# MCU.net
KiCad netlist of a schematic drawn in Altium Designer
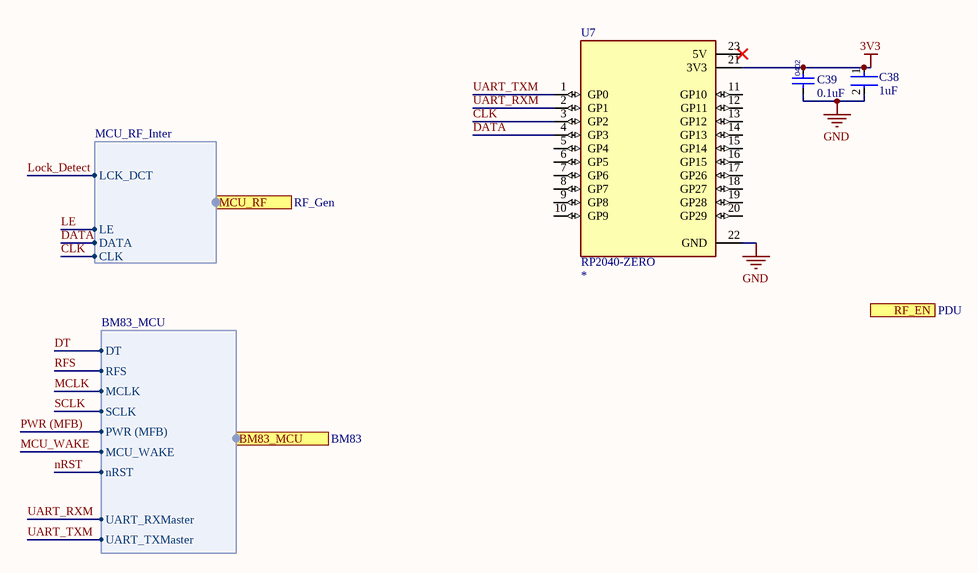
[diagram p0: MCU.SchDoc]

(export (version "E")
  (design (tool "Eeschema 10.0.6"))
  (components
    (comp (ref "C38")
      (value "1uF")
      (footprint "FP-GRM155-0_1-IPC_C")
      (libsource (lib "Altium Content Vault") (part "11868f565c42a9108669ba33697ecf6"))
    )
    (comp (ref "C39")
      (value "0.1uF")
      (footprint "FP-CC0402-IPC_B")
      (fields (field (name "TOLERANCE") "10%"))
      (libsource (lib "University of Wisconsin Formula FSAE") (part "0402 ceramic cap"))
    )
    (comp (ref "U7")
      (value "RP2040-ZERO")
      (footprint "MODULE_RP2040-ZERO")
      (description "Low-Cost, High-Performance Pico-Like MCU Board Based On Raspberry Pi Microcontroller RP2040")
      (fields (field (name "ALTIUM_VALUE") "*") (field (name "MF") "Waveshare Electronics"))
      (libsource (lib "University of Wisconsin Formula FSAE") (part "RP2040-ZERO"))
    )
  )
  (nets
    (net (code "3") (name "/CLK") (class "Default")
      (node (ref "U7") (pin "3") (pinfunction "GP2_3") (pintype "bidirectional"))
    )
    (net (code "4") (name "/DATA") (class "Default")
      (node (ref "U7") (pin "4") (pinfunction "GP3_4") (pintype "bidirectional"))
    )
    (net (code "14") (name "/UART_RXM") (class "Default")
      (node (ref "U7") (pin "2") (pinfunction "GP1_2") (pintype "bidirectional"))
    )
    (net (code "15") (name "/UART_TXM") (class "Default")
      (node (ref "U7") (pin "1") (pinfunction "GP0_1") (pintype "bidirectional"))
    )
    (net (code "19") (name "3V3") (class "Default")
      (node (ref "C38") (pin "1") (pinfunction "1_1") (pintype "passive"))
      (node (ref "C39") (pin "2") (pinfunction "2_2") (pintype "passive"))
      (node (ref "U7") (pin "21") (pinfunction "3V3_21") (pintype "power_in"))
    )
    (net (code "20") (name "GND") (class "Default")
      (node (ref "C38") (pin "2") (pinfunction "2_2") (pintype "passive"))
      (node (ref "C39") (pin "1") (pinfunction "1_1") (pintype "passive"))
      (node (ref "U7") (pin "22") (pinfunction "GND_22") (pintype "power_in"))
    )
    (net (code "21") (name "unconnected-(U7-5V-Pad23)") (class "Default")
      (node (ref "U7") (pin "23") (pinfunction "5V_23") (pintype "power_in+no_connect"))
    )
    (net (code "22") (name "unconnected-(U7-GP4-Pad5)") (class "Default")
      (node (ref "U7") (pin "5") (pinfunction "GP4_5") (pintype "bidirectional"))
    )
    (net (code "23") (name "unconnected-(U7-GP5-Pad6)") (class "Default")
      (node (ref "U7") (pin "6") (pinfunction "GP5_6") (pintype "bidirectional"))
    )
    (net (code "24") (name "unconnected-(U7-GP6-Pad7)") (class "Default")
      (node (ref "U7") (pin "7") (pinfunction "GP6_7") (pintype "bidirectional"))
    )
    (net (code "25") (name "unconnected-(U7-GP7-Pad8)") (class "Default")
      (node (ref "U7") (pin "8") (pinfunction "GP7_8") (pintype "bidirectional"))
    )
    (net (code "26") (name "unconnected-(U7-GP8-Pad9)") (class "Default")
      (node (ref "U7") (pin "9") (pinfunction "GP8_9") (pintype "bidirectional"))
    )
    (net (code "27") (name "unconnected-(U7-GP9-Pad10)") (class "Default")
      (node (ref "U7") (pin "10") (pinfunction "GP9_10") (pintype "bidirectional"))
    )
    (net (code "28") (name "unconnected-(U7-GP10-Pad11)") (class "Default")
      (node (ref "U7") (pin "11") (pinfunction "GP10_11") (pintype "bidirectional"))
    )
    (net (code "29") (name "unconnected-(U7-GP11-Pad12)") (class "Default")
      (node (ref "U7") (pin "12") (pinfunction "GP11_12") (pintype "bidirectional"))
    )
    (net (code "30") (name "unconnected-(U7-GP12-Pad13)") (class "Default")
      (node (ref "U7") (pin "13") (pinfunction "GP12_13") (pintype "bidirectional"))
    )
    (net (code "31") (name "unconnected-(U7-GP13-Pad14)") (class "Default")
      (node (ref "U7") (pin "14") (pinfunction "GP13_14") (pintype "bidirectional"))
    )
    (net (code "32") (name "unconnected-(U7-GP14-Pad15)") (class "Default")
      (node (ref "U7") (pin "15") (pinfunction "GP14_15") (pintype "bidirectional"))
    )
    (net (code "33") (name "unconnected-(U7-GP15-Pad16)") (class "Default")
      (node (ref "U7") (pin "16") (pinfunction "GP15_16") (pintype "bidirectional"))
    )
    (net (code "34") (name "unconnected-(U7-GP26-Pad17)") (class "Default")
      (node (ref "U7") (pin "17") (pinfunction "GP26_17") (pintype "bidirectional"))
    )
    (net (code "35") (name "unconnected-(U7-GP27-Pad18)") (class "Default")
      (node (ref "U7") (pin "18") (pinfunction "GP27_18") (pintype "bidirectional"))
    )
    (net (code "36") (name "unconnected-(U7-GP28-Pad19)") (class "Default")
      (node (ref "U7") (pin "19") (pinfunction "GP28_19") (pintype "bidirectional"))
    )
    (net (code "37") (name "unconnected-(U7-GP29-Pad20)") (class "Default")
      (node (ref "U7") (pin "20") (pinfunction "GP29_20") (pintype "bidirectional"))
    )
  )
)
